# Connector_Block.net
KiCad netlist of a schematic drawn in Altium Designer
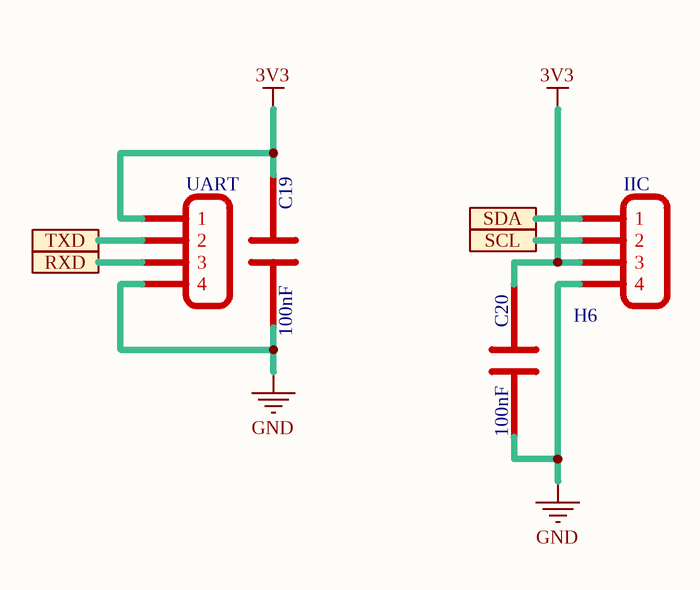
[diagram p0: Connector_Block.SchDoc]

(export (version "E")
  (design (tool "Eeschema 10.0.6"))
  (components
    (comp (ref "C19")
      (value "100nF")
      (footprint "C0805")
      (description "Ceramic Capacitor")
      (libsource (lib "CTAI-Library") (part "CAP-CER"))
    )
    (comp (ref "C20")
      (value "100nF")
      (footprint "C0805")
      (description "Ceramic Capacitor")
      (libsource (lib "CTAI-Library") (part "CAP-CER"))
    )
    (comp (ref "H5")
      (value "UART")
      (footprint "XH-2.54-4P")
      (description "Connector 4 Pole")
      (libsource (lib "CTAI-Library") (part "CONN-4P"))
    )
    (comp (ref "H6")
      (value "IIC")
      (footprint "XH-2.54-4P")
      (description "Connector 4 Pole")
      (libsource (lib "CTAI-Library") (part "CONN-4P"))
    )
  )
  (nets
    (net (code "1") (name "/RXD") (class "Default")
      (node (ref "H5") (pin "3") (pinfunction "3_3") (pintype "passive"))
    )
    (net (code "2") (name "/SCL") (class "Default")
      (node (ref "H6") (pin "2") (pinfunction "2_2") (pintype "passive"))
    )
    (net (code "3") (name "/SDA") (class "Default")
      (node (ref "H6") (pin "1") (pinfunction "1_1") (pintype "passive"))
    )
    (net (code "4") (name "/TXD") (class "Default")
      (node (ref "H5") (pin "2") (pinfunction "2_2") (pintype "passive"))
    )
    (net (code "5") (name "3V3") (class "Default")
      (node (ref "C19") (pin "2") (pintype "passive"))
      (node (ref "C20") (pin "2") (pintype "passive"))
      (node (ref "H5") (pin "1") (pinfunction "1_1") (pintype "passive"))
      (node (ref "H6") (pin "3") (pinfunction "3_3") (pintype "passive"))
    )
    (net (code "6") (name "GND") (class "Default")
      (node (ref "C19") (pin "1") (pintype "passive"))
      (node (ref "C20") (pin "1") (pintype "passive"))
      (node (ref "H5") (pin "4") (pinfunction "4_4") (pintype "passive"))
      (node (ref "H6") (pin "4") (pinfunction "4_4") (pintype "passive"))
    )
  )
)
